# MR_UartConnector.net
KiCad netlist of a schematic drawn in Altium Designer
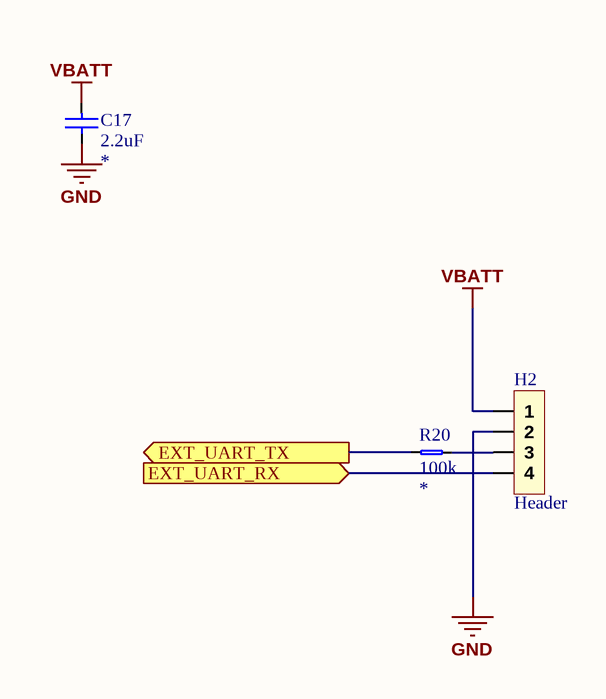
[diagram p0: MR_UartConnector.SchDoc]

(export (version "E")
  (design (tool "Eeschema 10.0.6"))
  (components
    (comp (ref "C17")
      (value "2.2uF")
      (footprint "0603_CAP_LD")
      (description "Ceramic Capacitor")
      (fields (field (name "PACKAGE") "*") (field (name "Comment") "CerCap"))
      (libsource (lib "MiniRobot") (part "CerCap"))
    )
    (comp (ref "H2")
      (value "Header")
      (footprint "HE14 1x4 Straight")
      (description "Header 4x1 PIns")
      (libsource (lib "MiniRobot") (part "Header_4x1"))
    )
    (comp (ref "R20")
      (value "100k")
      (footprint "0603_RES_LD")
      (description "Resistor")
      (fields (field (name "PACKAGE") "*"))
      (libsource (lib "MiniRobot") (part "Resistor"))
    )
  )
  (nets
    (net (code "1") (name "/EXT_UART_RX") (class "Default")
      (node (ref "H2") (pin "4") (pinfunction "4_4") (pintype "passive"))
    )
    (net (code "2") (name "/EXT_UART_TX") (class "Default")
      (node (ref "R20") (pin "1") (pinfunction "1_1") (pintype "passive"))
    )
    (net (code "3") (name "GND") (class "Default")
      (node (ref "C17") (pin "2") (pinfunction "2_2") (pintype "passive"))
      (node (ref "H2") (pin "2") (pinfunction "2_2") (pintype "passive"))
    )
    (net (code "4") (name "Net-(H2-Pad3)") (class "Default")
      (node (ref "H2") (pin "3") (pinfunction "3_3") (pintype "passive"))
      (node (ref "R20") (pin "2") (pinfunction "2_2") (pintype "passive"))
    )
    (net (code "5") (name "VBATT") (class "Default")
      (node (ref "C17") (pin "1") (pinfunction "1_1") (pintype "passive"))
      (node (ref "H2") (pin "1") (pinfunction "1_1") (pintype "passive"))
    )
  )
)
